# STLINK.net
KiCad netlist of a schematic drawn in Altium Designer
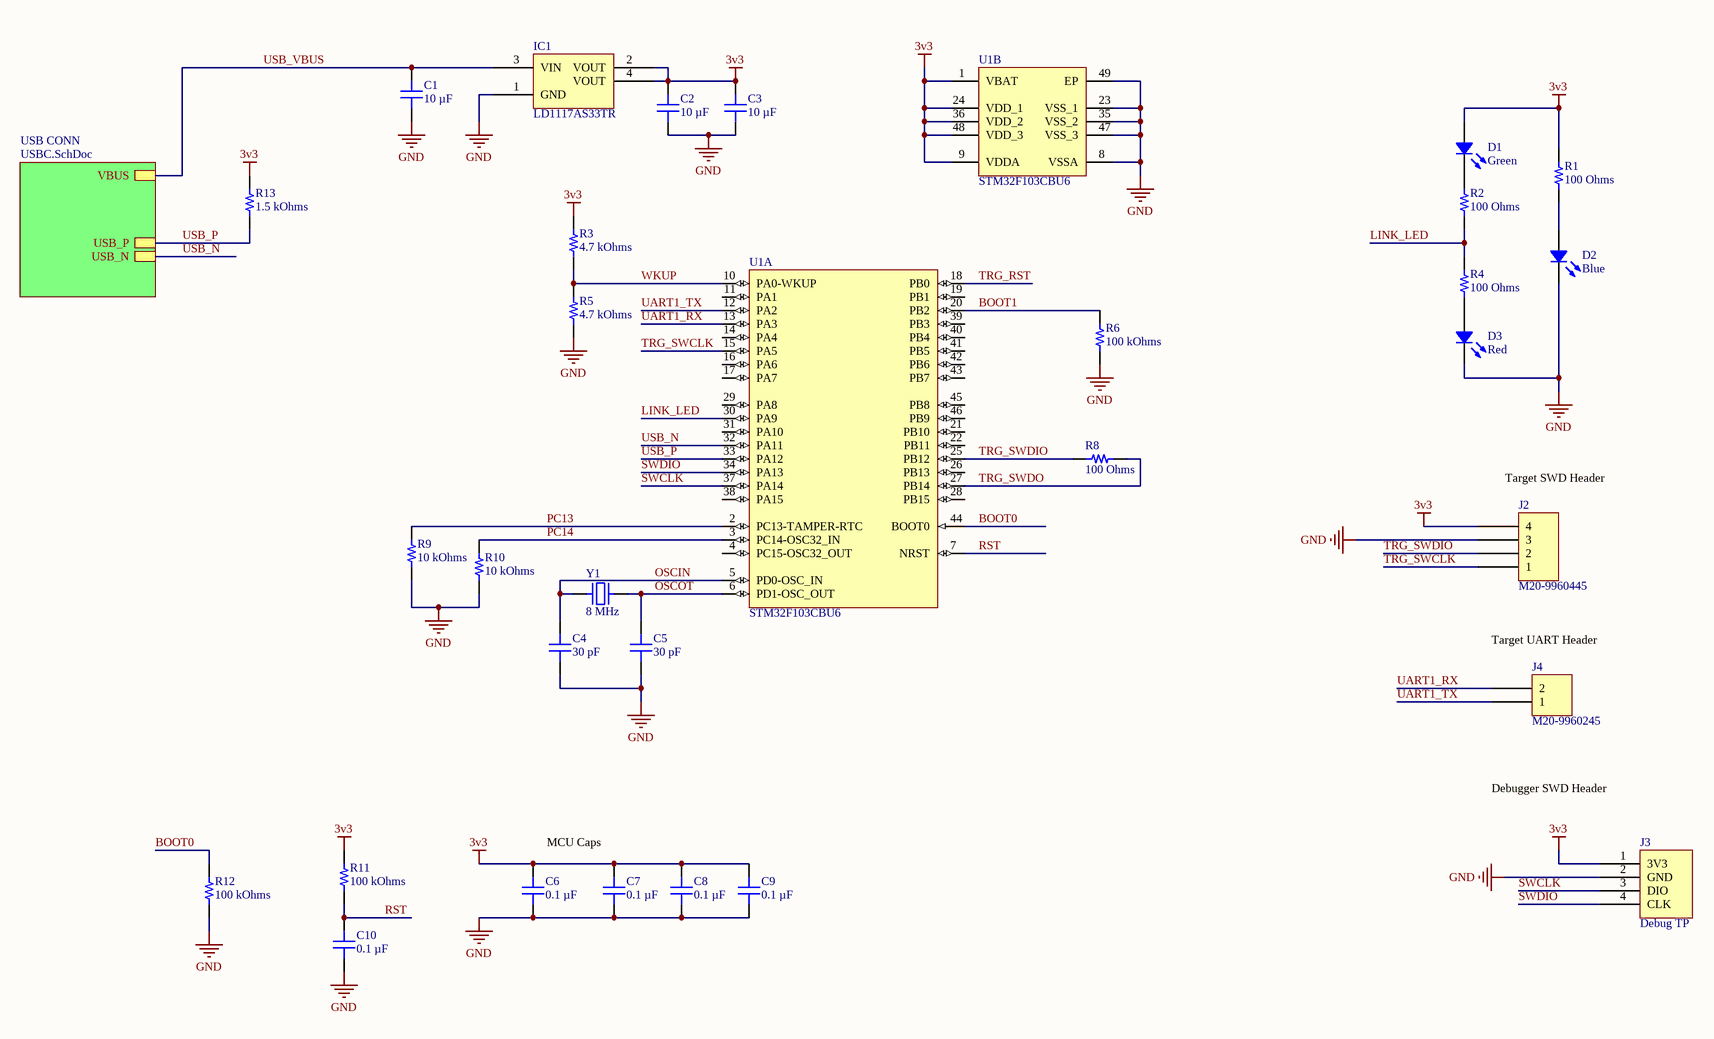
[diagram p0: STLINK.SchDoc]

(export (version "E")
  (design (tool "Eeschema 10.0.6"))
  (components
    (comp (ref "C1")
      (value "10 µF")
      (footprint "CAP 0603_1608")
      (description "CAP0603 X5R 10UF 20% 10V")
      (fields
        (field (name "PART NUMBER") "GMC10X5R106M10NT")
        (field (name "MANUFACTURER") "Cal-Chip Electronics, Inc.")
      )
      (libsource (lib "Celestial Altium Library - altium_library") (part "Capacitor"))
    )
    (comp (ref "C2")
      (value "10 µF")
      (footprint "CAP 0603_1608")
      (description "CAP0603 X5R 10UF 20% 10V")
      (fields
        (field (name "PART NUMBER") "GMC10X5R106M10NT")
        (field (name "MANUFACTURER") "Cal-Chip Electronics, Inc.")
      )
      (libsource (lib "Celestial Altium Library - altium_library") (part "Capacitor"))
    )
    (comp (ref "C3")
      (value "10 µF")
      (footprint "CAP 0603_1608")
      (description "CAP0603 X5R 10UF 20% 10V")
      (fields
        (field (name "PART NUMBER") "GMC10X5R106M10NT")
        (field (name "MANUFACTURER") "Cal-Chip Electronics, Inc.")
      )
      (libsource (lib "Celestial Altium Library - altium_library") (part "Capacitor"))
    )
    (comp (ref "C4")
      (value "30 pF")
      (footprint "CAP 0603_1608")
      (description "CAP CER 30PF 50V C0G/NP0 0603")
      (fields
        (field (name "PART NUMBER") "0603N300J500CT")
        (field (name "MANUFACTURER") "Walsin Technology Corporation")
      )
      (libsource (lib "Celestial Altium Library - altium_library") (part "Capacitor"))
    )
    (comp (ref "C5")
      (value "30 pF")
      (footprint "CAP 0603_1608")
      (description "CAP CER 30PF 50V C0G/NP0 0603")
      (fields
        (field (name "PART NUMBER") "0603N300J500CT")
        (field (name "MANUFACTURER") "Walsin Technology Corporation")
      )
      (libsource (lib "Celestial Altium Library - altium_library") (part "Capacitor"))
    )
    (comp (ref "C6")
      (value "0.1 µF")
      (footprint "CAP 0603_1608")
      (description "CAP0603 X7R .1UF 10% 25V")
      (fields
        (field (name "PART NUMBER") "GMC10X7R104K25NT")
        (field (name "MANUFACTURER") "Cal-Chip Electronics, Inc.")
      )
      (libsource (lib "Celestial Altium Library - altium_library") (part "Capacitor"))
    )
    (comp (ref "C7")
      (value "0.1 µF")
      (footprint "CAP 0603_1608")
      (description "CAP0603 X7R .1UF 10% 25V")
      (fields
        (field (name "PART NUMBER") "GMC10X7R104K25NT")
        (field (name "MANUFACTURER") "Cal-Chip Electronics, Inc.")
      )
      (libsource (lib "Celestial Altium Library - altium_library") (part "Capacitor"))
    )
    (comp (ref "C8")
      (value "0.1 µF")
      (footprint "CAP 0603_1608")
      (description "CAP0603 X7R .1UF 10% 25V")
      (fields
        (field (name "PART NUMBER") "GMC10X7R104K25NT")
        (field (name "MANUFACTURER") "Cal-Chip Electronics, Inc.")
      )
      (libsource (lib "Celestial Altium Library - altium_library") (part "Capacitor"))
    )
    (comp (ref "C9")
      (value "0.1 µF")
      (footprint "CAP 0603_1608")
      (description "CAP0603 X7R .1UF 10% 25V")
      (fields
        (field (name "PART NUMBER") "GMC10X7R104K25NT")
        (field (name "MANUFACTURER") "Cal-Chip Electronics, Inc.")
      )
      (libsource (lib "Celestial Altium Library - altium_library") (part "Capacitor"))
    )
    (comp (ref "C10")
      (value "0.1 µF")
      (footprint "CAP 0603_1608")
      (description "CAP0603 X7R .1UF 10% 25V")
      (fields
        (field (name "PART NUMBER") "GMC10X7R104K25NT")
        (field (name "MANUFACTURER") "Cal-Chip Electronics, Inc.")
      )
      (libsource (lib "Celestial Altium Library - altium_library") (part "Capacitor"))
    )
    (comp (ref "D1")
      (value "Green")
      (footprint "LED 0603_1608 GREEN")
      (description "LED GREEN CLEAR 2SMD")
      (fields
        (field (name "PART NUMBER") "19-213/GVC-AMNB/3T")
        (field (name "MANUFACTURER") "Everlight Electronics Co Ltd")
      )
      (libsource (lib "Celestial Altium Library - altium_library") (part "LED"))
    )
    (comp (ref "D2")
      (value "Blue")
      (footprint "LED 0603_1608 BLUE")
      (description "LED BLUE CLEAR 2SMD")
      (fields
        (field (name "PART NUMBER") "19-217/B7C-ZL2N1B3X/3T")
        (field (name "MANUFACTURER") "Everlight Electronics Co Ltd")
      )
      (libsource (lib "Celestial Altium Library - altium_library") (part "LED"))
    )
    (comp (ref "D3")
      (value "Red")
      (footprint "LED 0603_1608 RED")
      (description "LED RED CLEAR 2SMD")
      (fields
        (field (name "PART NUMBER") "19-213SDRC/S259/TR8")
        (field (name "MANUFACTURER") "Everlight Electronics Co Ltd")
      )
      (libsource (lib "Celestial Altium Library - altium_library") (part "LED"))
    )
    (comp (ref "IC1")
      (value "LD1117AS33TR")
      (footprint "ST SOT-223")
      (description "IC REG LINEAR 3.3V 1A SOT223")
      (fields (field (name "MANUFACTURER") "STMicroelectronics"))
      (libsource (lib "Celestial Altium Library - altium_library") (part "ST LD1117"))
    )
    (comp (ref "J2")
      (value "M20-9960445")
      (footprint "HARWIN M20-9960445")
      (description "CONN HEADER R/A 4POS 2.54MM")
      (fields (field (name "MANUFACTURER") "Harwin Inc."))
      (libsource (lib "Celestial Altium Library - altium_library") (part "4 Pin"))
    )
    (comp (ref "J3")
      (value "Debug TP")
      (footprint "CAPC2121X00N")
      (description "ST-Link Test Point")
      (libsource (lib "Queens University - FSAE") (part "New symbol 1"))
    )
    (comp (ref "J4")
      (value "M20-9960245")
      (footprint "HARWIN M20-9960245")
      (description "CONN HEADER R/A 2POS 2.54MM")
      (fields (field (name "MANUFACTURER") "Harwin Inc."))
      (libsource (lib "Celestial Altium Library - altium_library") (part "2 Pin"))
    )
    (comp (ref "R1")
      (value "100 Ohms")
      (footprint "RES 0603_1608")
      (description "RCA0603 100R 5% 200 ET1 E3")
      (fields (field (name "PART NUMBER") "RCA0603100RJNEA") (field (name "MANUFACTURER") "Vishay Dale"))
      (libsource (lib "Celestial Altium Library - altium_library") (part "Resistor"))
    )
    (comp (ref "R2")
      (value "100 Ohms")
      (footprint "RES 0603_1608")
      (description "RCA0603 100R 5% 200 ET1 E3")
      (fields (field (name "PART NUMBER") "RCA0603100RJNEA") (field (name "MANUFACTURER") "Vishay Dale"))
      (libsource (lib "Celestial Altium Library - altium_library") (part "Resistor"))
    )
    (comp (ref "R3")
      (value "4.7 kOhms")
      (footprint "RES 0603_1608")
      (description "RES 4.7K OHM 0.05% 1/8W 0603")
      (fields
        (field (name "PART NUMBER") "ERA-3VRW4701V")
        (field (name "MANUFACTURER") "Panasonic Electronic Components")
      )
      (libsource (lib "Celestial Altium Library - altium_library") (part "Resistor"))
    )
    (comp (ref "R4")
      (value "100 Ohms")
      (footprint "RES 0603_1608")
      (description "RCA0603 100R 5% 200 ET1 E3")
      (fields (field (name "PART NUMBER") "RCA0603100RJNEA") (field (name "MANUFACTURER") "Vishay Dale"))
      (libsource (lib "Celestial Altium Library - altium_library") (part "Resistor"))
    )
    (comp (ref "R5")
      (value "4.7 kOhms")
      (footprint "RES 0603_1608")
      (description "RES 4.7K OHM 0.05% 1/8W 0603")
      (fields
        (field (name "PART NUMBER") "ERA-3VRW4701V")
        (field (name "MANUFACTURER") "Panasonic Electronic Components")
      )
      (libsource (lib "Celestial Altium Library - altium_library") (part "Resistor"))
    )
    (comp (ref "R6")
      (value "100 kOhms")
      (footprint "RES 0603_1608")
      (description "MCT 0603-05 0.1% AT P5 100K")
      (fields
        (field (name "PART NUMBER") "MCT0603MG1003BP500")
        (field (name "MANUFACTURER") "Vishay Beyschlag/Draloric/BC Components")
      )
      (libsource (lib "Celestial Altium Library - altium_library") (part "Resistor"))
    )
    (comp (ref "R8")
      (value "100 Ohms")
      (footprint "RES 0603_1608")
      (description "RCA0603 100R 5% 200 ET1 E3")
      (fields (field (name "PART NUMBER") "RCA0603100RJNEA") (field (name "MANUFACTURER") "Vishay Dale"))
      (libsource (lib "Celestial Altium Library - altium_library") (part "Resistor"))
    )
    (comp (ref "R9")
      (value "10 kOhms")
      (footprint "RES 0603_1608")
      (description "MCT 0603-05 0.1% AT P5 10K")
      (fields
        (field (name "PART NUMBER") "MCT0603MG1002BP500")
        (field (name "MANUFACTURER") "Vishay Beyschlag/Draloric/BC Components")
      )
      (libsource (lib "Celestial Altium Library - altium_library") (part "Resistor"))
    )
    (comp (ref "R10")
      (value "10 kOhms")
      (footprint "RES 0603_1608")
      (description "MCT 0603-05 0.1% AT P5 10K")
      (fields
        (field (name "PART NUMBER") "MCT0603MG1002BP500")
        (field (name "MANUFACTURER") "Vishay Beyschlag/Draloric/BC Components")
      )
      (libsource (lib "Celestial Altium Library - altium_library") (part "Resistor"))
    )
    (comp (ref "R11")
      (value "100 kOhms")
      (footprint "RES 0603_1608")
      (description "MCT 0603-05 0.1% AT P5 100K")
      (fields
        (field (name "PART NUMBER") "MCT0603MG1003BP500")
        (field (name "MANUFACTURER") "Vishay Beyschlag/Draloric/BC Components")
      )
      (libsource (lib "Celestial Altium Library - altium_library") (part "Resistor"))
    )
    (comp (ref "R12")
      (value "100 kOhms")
      (footprint "RES 0603_1608")
      (description "MCT 0603-05 0.1% AT P5 100K")
      (fields
        (field (name "PART NUMBER") "MCT0603MG1003BP500")
        (field (name "MANUFACTURER") "Vishay Beyschlag/Draloric/BC Components")
      )
      (libsource (lib "Celestial Altium Library - altium_library") (part "Resistor"))
    )
    (comp (ref "R13")
      (value "1.5 kOhms")
      (footprint "RES 0603_1608")
      (description "PTN0603 10PPM 1.5K 0.1% S T1 E1")
      (fields
        (field (name "PART NUMBER") "PTN0603Y1501BST1")
        (field (name "MANUFACTURER") "Vishay Dale Thin Film")
      )
      (libsource (lib "Celestial Altium Library - altium_library") (part "Resistor"))
    )
    (comp (ref "U1")
      (value "STM32F103CBU6")
      (footprint "STM-UFQFPN48_N")
      (libsource (lib "Altium Content Vault") (part "MC-ARM-STM32F103X8_B-SQ49"))
    )
    (comp (ref "Y1")
      (value "8 MHz")
      (footprint "NDK NX3225GD")
      (description "CRYSTAL 8.0000MHZ 8PF SMD")
      (fields
        (field (name "PART NUMBER") "NX3225GD-8MHZ-EXS00A-CG04874")
        (field (name "MANUFACTURER") "NDK America, Inc.")
      )
      (libsource (lib "Celestial Altium Library - altium_library") (part "NDK NX3225GD"))
    )
  )
  (nets
    (net (code "1") (name "/BOOT0") (class "Default")
      (node (ref "R12") (pin "2") (pinfunction "2_2") (pintype "passive"))
      (node (ref "U1") (pin "44") (pinfunction "BOOT0_44") (pintype "input"))
    )
    (net (code "2") (name "/BOOT1") (class "Default")
      (node (ref "R6") (pin "2") (pinfunction "2_2") (pintype "passive"))
      (node (ref "U1") (pin "20") (pinfunction "PB2_20") (pintype "bidirectional"))
    )
    (net (code "3") (name "/LINK_LED") (class "Default")
      (node (ref "R2") (pin "1") (pinfunction "1_1") (pintype "passive"))
      (node (ref "R4") (pin "2") (pinfunction "2_2") (pintype "passive"))
      (node (ref "U1") (pin "30") (pinfunction "PA9_30") (pintype "bidirectional"))
    )
    (net (code "4") (name "/OSCIN") (class "Default")
      (node (ref "C4") (pin "2") (pinfunction "2_2") (pintype "passive"))
      (node (ref "U1") (pin "5") (pinfunction "PD0-OSC_IN_5") (pintype "bidirectional"))
      (node (ref "Y1") (pin "1") (pinfunction "1_1") (pintype "passive"))
    )
    (net (code "5") (name "/OSCOT") (class "Default")
      (node (ref "C5") (pin "2") (pinfunction "2_2") (pintype "passive"))
      (node (ref "U1") (pin "6") (pinfunction "PD1-OSC_OUT_6") (pintype "bidirectional"))
      (node (ref "Y1") (pin "2") (pinfunction "2_2") (pintype "passive"))
    )
    (net (code "6") (name "/PC13") (class "Default")
      (node (ref "R9") (pin "2") (pinfunction "2_2") (pintype "passive"))
      (node (ref "U1") (pin "2") (pinfunction "PC13-TAMPER-RTC_2") (pintype "bidirectional"))
    )
    (net (code "7") (name "/PC14") (class "Default")
      (node (ref "R10") (pin "2") (pinfunction "2_2") (pintype "passive"))
      (node (ref "U1") (pin "3") (pinfunction "PC14-OSC32_IN_3") (pintype "bidirectional"))
    )
    (net (code "8") (name "/RST") (class "Default")
      (node (ref "C10") (pin "2") (pinfunction "2_2") (pintype "passive"))
      (node (ref "R11") (pin "1") (pinfunction "1_1") (pintype "passive"))
      (node (ref "U1") (pin "7") (pinfunction "NRST_7") (pintype "bidirectional"))
    )
    (net (code "9") (name "/SWCLK") (class "Default")
      (node (ref "J3") (pin "3") (pinfunction "DIO_3") (pintype "passive"))
      (node (ref "U1") (pin "37") (pinfunction "PA14_37") (pintype "bidirectional"))
    )
    (net (code "10") (name "/SWDIO") (class "Default")
      (node (ref "J3") (pin "4") (pinfunction "CLK_4") (pintype "passive"))
      (node (ref "U1") (pin "34") (pinfunction "PA13_34") (pintype "bidirectional"))
    )
    (net (code "11") (name "/TRG_RST") (class "Default")
      (node (ref "U1") (pin "18") (pinfunction "PB0_18") (pintype "bidirectional"))
    )
    (net (code "12") (name "/TRG_SWCLK") (class "Default")
      (node (ref "J2") (pin "1") (pinfunction "1_1") (pintype "passive"))
      (node (ref "U1") (pin "15") (pinfunction "PA5_15") (pintype "bidirectional"))
    )
    (net (code "13") (name "/TRG_SWDIO") (class "Default")
      (node (ref "J2") (pin "2") (pinfunction "2_2") (pintype "passive"))
      (node (ref "R8") (pin "1") (pinfunction "1_1") (pintype "passive"))
      (node (ref "U1") (pin "25") (pinfunction "PB12_25") (pintype "bidirectional"))
    )
    (net (code "14") (name "/TRG_SWDO") (class "Default")
      (node (ref "R8") (pin "2") (pinfunction "2_2") (pintype "passive"))
      (node (ref "U1") (pin "27") (pinfunction "PB14_27") (pintype "bidirectional"))
    )
    (net (code "15") (name "/UART1_RX") (class "Default")
      (node (ref "J4") (pin "2") (pinfunction "2_2") (pintype "passive"))
      (node (ref "U1") (pin "13") (pinfunction "PA3_13") (pintype "bidirectional"))
    )
    (net (code "16") (name "/UART1_TX") (class "Default")
      (node (ref "J4") (pin "1") (pinfunction "1_1") (pintype "passive"))
      (node (ref "U1") (pin "12") (pinfunction "PA2_12") (pintype "bidirectional"))
    )
    (net (code "17") (name "/USB_N") (class "Default")
      (node (ref "U1") (pin "32") (pinfunction "PA11_32") (pintype "bidirectional"))
    )
    (net (code "18") (name "/USB_P") (class "Default")
      (node (ref "R13") (pin "1") (pinfunction "1_1") (pintype "passive"))
      (node (ref "U1") (pin "33") (pinfunction "PA12_33") (pintype "bidirectional"))
    )
    (net (code "19") (name "/USB_VBUS") (class "Default")
      (node (ref "C1") (pin "2") (pinfunction "2_2") (pintype "passive"))
      (node (ref "IC1") (pin "3") (pinfunction "VIN_3") (pintype "passive"))
    )
    (net (code "20") (name "/WKUP") (class "Default")
      (node (ref "R3") (pin "1") (pinfunction "1_1") (pintype "passive"))
      (node (ref "R5") (pin "2") (pinfunction "2_2") (pintype "passive"))
      (node (ref "U1") (pin "10") (pinfunction "PA0-WKUP_10") (pintype "bidirectional"))
    )
    (net (code "21") (name "3v3") (class "Default")
      (node (ref "C2") (pin "2") (pinfunction "2_2") (pintype "passive"))
      (node (ref "C3") (pin "2") (pinfunction "2_2") (pintype "passive"))
      (node (ref "C6") (pin "2") (pinfunction "2_2") (pintype "passive"))
      (node (ref "C7") (pin "2") (pinfunction "2_2") (pintype "passive"))
      (node (ref "C8") (pin "2") (pinfunction "2_2") (pintype "passive"))
      (node (ref "C9") (pin "2") (pinfunction "2_2") (pintype "passive"))
      (node (ref "D1") (pin "1") (pinfunction "1_1") (pintype "passive"))
      (node (ref "IC1") (pin "2") (pinfunction "VOUT_2") (pintype "passive"))
      (node (ref "IC1") (pin "4") (pinfunction "VOUT_4") (pintype "passive"))
      (node (ref "J2") (pin "4") (pinfunction "4_4") (pintype "passive"))
      (node (ref "J3") (pin "1") (pinfunction "3V3_1") (pintype "passive"))
      (node (ref "R1") (pin "2") (pinfunction "2_2") (pintype "passive"))
      (node (ref "R11") (pin "2") (pinfunction "2_2") (pintype "passive"))
      (node (ref "R13") (pin "2") (pinfunction "2_2") (pintype "passive"))
      (node (ref "R3") (pin "2") (pinfunction "2_2") (pintype "passive"))
      (node (ref "U1") (pin "1") (pinfunction "VBAT_1") (pintype "power_in"))
      (node (ref "U1") (pin "24") (pinfunction "VDD_1_24") (pintype "power_in"))
      (node (ref "U1") (pin "36") (pinfunction "VDD_2_36") (pintype "power_in"))
      (node (ref "U1") (pin "48") (pinfunction "VDD_3_48") (pintype "power_in"))
      (node (ref "U1") (pin "9") (pinfunction "VDDA_9") (pintype "power_in"))
    )
    (net (code "22") (name "GND") (class "Default")
      (node (ref "C1") (pin "1") (pinfunction "1_1") (pintype "passive"))
      (node (ref "C10") (pin "1") (pinfunction "1_1") (pintype "passive"))
      (node (ref "C2") (pin "1") (pinfunction "1_1") (pintype "passive"))
      (node (ref "C3") (pin "1") (pinfunction "1_1") (pintype "passive"))
      (node (ref "C4") (pin "1") (pinfunction "1_1") (pintype "passive"))
      (node (ref "C5") (pin "1") (pinfunction "1_1") (pintype "passive"))
      (node (ref "C6") (pin "1") (pinfunction "1_1") (pintype "passive"))
      (node (ref "C7") (pin "1") (pinfunction "1_1") (pintype "passive"))
      (node (ref "C8") (pin "1") (pinfunction "1_1") (pintype "passive"))
      (node (ref "C9") (pin "1") (pinfunction "1_1") (pintype "passive"))
      (node (ref "D2") (pin "2") (pinfunction "2_2") (pintype "passive"))
      (node (ref "D3") (pin "2") (pinfunction "2_2") (pintype "passive"))
      (node (ref "IC1") (pin "1") (pinfunction "GND_1") (pintype "passive"))
      (node (ref "J2") (pin "3") (pinfunction "3_3") (pintype "passive"))
      (node (ref "J3") (pin "2") (pinfunction "GND_2") (pintype "passive"))
      (node (ref "R10") (pin "1") (pinfunction "1_1") (pintype "passive"))
      (node (ref "R12") (pin "1") (pinfunction "1_1") (pintype "passive"))
      (node (ref "R5") (pin "1") (pinfunction "1_1") (pintype "passive"))
      (node (ref "R6") (pin "1") (pinfunction "1_1") (pintype "passive"))
      (node (ref "R9") (pin "1") (pinfunction "1_1") (pintype "passive"))
      (node (ref "U1") (pin "23") (pinfunction "VSS_1_23") (pintype "power_in"))
      (node (ref "U1") (pin "35") (pinfunction "VSS_2_35") (pintype "power_in"))
      (node (ref "U1") (pin "47") (pinfunction "VSS_3_47") (pintype "power_in"))
      (node (ref "U1") (pin "49") (pinfunction "EP_49") (pintype "power_in"))
      (node (ref "U1") (pin "8") (pinfunction "VSSA_8") (pintype "power_in"))
    )
    (net (code "23") (name "Net-(D1-Pad2)") (class "Default")
      (node (ref "D1") (pin "2") (pinfunction "2_2") (pintype "passive"))
      (node (ref "R2") (pin "2") (pinfunction "2_2") (pintype "passive"))
    )
    (net (code "24") (name "Net-(D2-Pad1)") (class "Default")
      (node (ref "D2") (pin "1") (pinfunction "1_1") (pintype "passive"))
      (node (ref "R1") (pin "1") (pinfunction "1_1") (pintype "passive"))
    )
    (net (code "25") (name "Net-(D3-Pad1)") (class "Default")
      (node (ref "D3") (pin "1") (pinfunction "1_1") (pintype "passive"))
      (node (ref "R4") (pin "1") (pinfunction "1_1") (pintype "passive"))
    )
    (net (code "26") (name "unconnected-(U1A-PA1-Pad11)") (class "Default")
      (node (ref "U1") (pin "11") (pinfunction "PA1_11") (pintype "bidirectional"))
    )
    (net (code "27") (name "unconnected-(U1A-PA4-Pad14)") (class "Default")
      (node (ref "U1") (pin "14") (pinfunction "PA4_14") (pintype "bidirectional"))
    )
    (net (code "28") (name "unconnected-(U1A-PA6-Pad16)") (class "Default")
      (node (ref "U1") (pin "16") (pinfunction "PA6_16") (pintype "bidirectional"))
    )
    (net (code "29") (name "unconnected-(U1A-PA7-Pad17)") (class "Default")
      (node (ref "U1") (pin "17") (pinfunction "PA7_17") (pintype "bidirectional"))
    )
    (net (code "30") (name "unconnected-(U1A-PA8-Pad29)") (class "Default")
      (node (ref "U1") (pin "29") (pinfunction "PA8_29") (pintype "bidirectional"))
    )
    (net (code "31") (name "unconnected-(U1A-PA10-Pad31)") (class "Default")
      (node (ref "U1") (pin "31") (pinfunction "PA10_31") (pintype "bidirectional"))
    )
    (net (code "32") (name "unconnected-(U1A-PA15-Pad38)") (class "Default")
      (node (ref "U1") (pin "38") (pinfunction "PA15_38") (pintype "bidirectional"))
    )
    (net (code "33") (name "unconnected-(U1A-PB1-Pad19)") (class "Default")
      (node (ref "U1") (pin "19") (pinfunction "PB1_19") (pintype "bidirectional"))
    )
    (net (code "34") (name "unconnected-(U1A-PB3-Pad39)") (class "Default")
      (node (ref "U1") (pin "39") (pinfunction "PB3_39") (pintype "bidirectional"))
    )
    (net (code "35") (name "unconnected-(U1A-PB4-Pad40)") (class "Default")
      (node (ref "U1") (pin "40") (pinfunction "PB4_40") (pintype "bidirectional"))
    )
    (net (code "36") (name "unconnected-(U1A-PB5-Pad41)") (class "Default")
      (node (ref "U1") (pin "41") (pinfunction "PB5_41") (pintype "bidirectional"))
    )
    (net (code "37") (name "unconnected-(U1A-PB6-Pad42)") (class "Default")
      (node (ref "U1") (pin "42") (pinfunction "PB6_42") (pintype "bidirectional"))
    )
    (net (code "38") (name "unconnected-(U1A-PB7-Pad43)") (class "Default")
      (node (ref "U1") (pin "43") (pinfunction "PB7_43") (pintype "bidirectional"))
    )
    (net (code "39") (name "unconnected-(U1A-PB8-Pad45)") (class "Default")
      (node (ref "U1") (pin "45") (pinfunction "PB8_45") (pintype "bidirectional"))
    )
    (net (code "40") (name "unconnected-(U1A-PB9-Pad46)") (class "Default")
      (node (ref "U1") (pin "46") (pinfunction "PB9_46") (pintype "bidirectional"))
    )
    (net (code "41") (name "unconnected-(U1A-PB10-Pad21)") (class "Default")
      (node (ref "U1") (pin "21") (pinfunction "PB10_21") (pintype "bidirectional"))
    )
    (net (code "42") (name "unconnected-(U1A-PB11-Pad22)") (class "Default")
      (node (ref "U1") (pin "22") (pinfunction "PB11_22") (pintype "bidirectional"))
    )
    (net (code "43") (name "unconnected-(U1A-PB13-Pad26)") (class "Default")
      (node (ref "U1") (pin "26") (pinfunction "PB13_26") (pintype "bidirectional"))
    )
    (net (code "44") (name "unconnected-(U1A-PB15-Pad28)") (class "Default")
      (node (ref "U1") (pin "28") (pinfunction "PB15_28") (pintype "bidirectional"))
    )
    (net (code "45") (name "unconnected-(U1A-PC15-OSC32_OUT-Pad4)") (class "Default")
      (node (ref "U1") (pin "4") (pinfunction "PC15-OSC32_OUT_4") (pintype "bidirectional"))
    )
  )
)
